# SolarPanelWithLongSide.net
KiCad netlist of a schematic drawn in Altium Designer
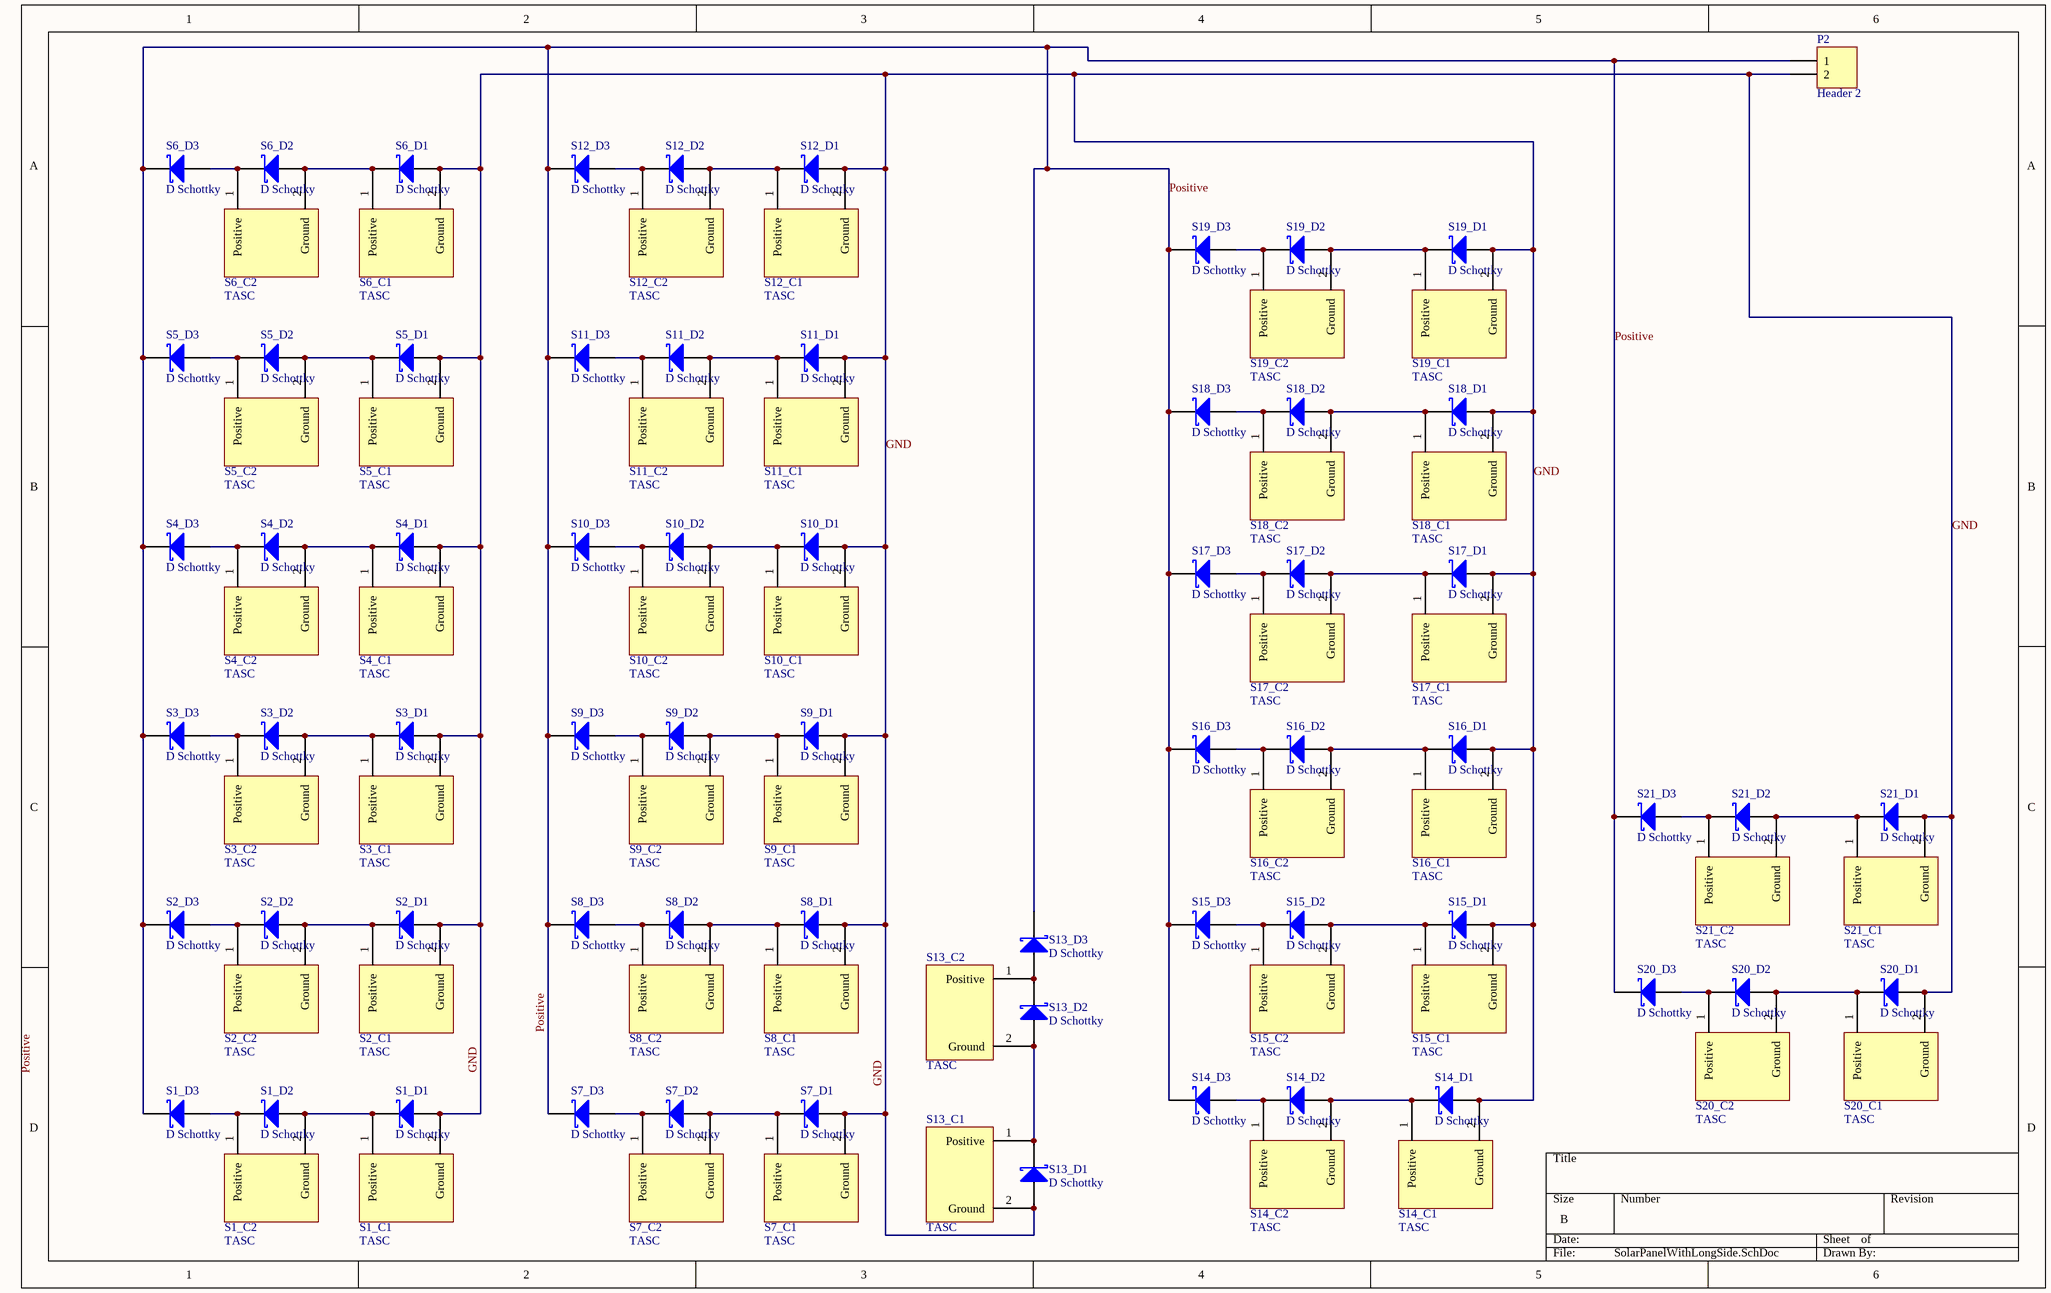
[diagram p0: SolarPanelWithLongSide.SchDoc]

(export (version "E")
  (design (tool "Eeschema 10.0.6"))
  (components
    (comp (ref "P2")
      (value "Header 2")
      (footprint "HDR1X2")
      (description "Header, 2-Pin")
      (fields (field (name "PUBLISHER") "Altium Limited"))
      (libsource (lib "Miscellaneous Connectors") (part "Header 2"))
    )
    (comp (ref "S1_C1")
      (value "TASC")
      (footprint "PCBComponent_1")
      (description "TASC Solar Cell")
      (libsource (lib "SolarPanel1") (part "TASC"))
    )
    (comp (ref "S1_C2")
      (value "TASC")
      (footprint "PCBComponent_1")
      (description "TASC Solar Cell")
      (libsource (lib "SolarPanel1") (part "TASC"))
    )
    (comp (ref "S1_D1")
      (value "D Schottky")
      (footprint "SMB")
      (description "Schottky Diode")
      (fields (field (name "PUBLISHER") "Altium Limited"))
      (libsource (lib "Miscellaneous Devices") (part "D Schottky"))
    )
    (comp (ref "S1_D2")
      (value "D Schottky")
      (footprint "SMB")
      (description "Schottky Diode")
      (fields (field (name "PUBLISHER") "Altium Limited"))
      (libsource (lib "Miscellaneous Devices") (part "D Schottky"))
    )
    (comp (ref "S1_D3")
      (value "D Schottky")
      (footprint "SMB")
      (description "Schottky Diode")
      (fields (field (name "PUBLISHER") "Altium Limited"))
      (libsource (lib "Miscellaneous Devices") (part "D Schottky"))
    )
    (comp (ref "S2_C1")
      (value "TASC")
      (footprint "PCBComponent_1")
      (description "TASC Solar Cell")
      (libsource (lib "SolarPanel1") (part "TASC"))
    )
    (comp (ref "S2_C2")
      (value "TASC")
      (footprint "PCBComponent_1")
      (description "TASC Solar Cell")
      (libsource (lib "SolarPanel1") (part "TASC"))
    )
    (comp (ref "S2_D1")
      (value "D Schottky")
      (footprint "SMB")
      (description "Schottky Diode")
      (fields (field (name "PUBLISHER") "Altium Limited"))
      (libsource (lib "Miscellaneous Devices") (part "D Schottky"))
    )
    (comp (ref "S2_D2")
      (value "D Schottky")
      (footprint "SMB")
      (description "Schottky Diode")
      (fields (field (name "PUBLISHER") "Altium Limited"))
      (libsource (lib "Miscellaneous Devices") (part "D Schottky"))
    )
    (comp (ref "S2_D3")
      (value "D Schottky")
      (footprint "SMB")
      (description "Schottky Diode")
      (fields (field (name "PUBLISHER") "Altium Limited"))
      (libsource (lib "Miscellaneous Devices") (part "D Schottky"))
    )
    (comp (ref "S3_C1")
      (value "TASC")
      (footprint "PCBComponent_1")
      (description "TASC Solar Cell")
      (libsource (lib "SolarPanel1") (part "TASC"))
    )
    (comp (ref "S3_C2")
      (value "TASC")
      (footprint "PCBComponent_1")
      (description "TASC Solar Cell")
      (libsource (lib "SolarPanel1") (part "TASC"))
    )
    (comp (ref "S3_D1")
      (value "D Schottky")
      (footprint "SMB")
      (description "Schottky Diode")
      (fields (field (name "PUBLISHER") "Altium Limited"))
      (libsource (lib "Miscellaneous Devices") (part "D Schottky"))
    )
    (comp (ref "S3_D2")
      (value "D Schottky")
      (footprint "SMB")
      (description "Schottky Diode")
      (fields (field (name "PUBLISHER") "Altium Limited"))
      (libsource (lib "Miscellaneous Devices") (part "D Schottky"))
    )
    (comp (ref "S3_D3")
      (value "D Schottky")
      (footprint "SMB")
      (description "Schottky Diode")
      (fields (field (name "PUBLISHER") "Altium Limited"))
      (libsource (lib "Miscellaneous Devices") (part "D Schottky"))
    )
    (comp (ref "S4_C1")
      (value "TASC")
      (footprint "PCBComponent_1")
      (description "TASC Solar Cell")
      (libsource (lib "SolarPanel1") (part "TASC"))
    )
    (comp (ref "S4_C2")
      (value "TASC")
      (footprint "PCBComponent_1")
      (description "TASC Solar Cell")
      (libsource (lib "SolarPanel1") (part "TASC"))
    )
    (comp (ref "S4_D1")
      (value "D Schottky")
      (footprint "SMB")
      (description "Schottky Diode")
      (fields (field (name "PUBLISHER") "Altium Limited"))
      (libsource (lib "Miscellaneous Devices") (part "D Schottky"))
    )
    (comp (ref "S4_D2")
      (value "D Schottky")
      (footprint "SMB")
      (description "Schottky Diode")
      (fields (field (name "PUBLISHER") "Altium Limited"))
      (libsource (lib "Miscellaneous Devices") (part "D Schottky"))
    )
    (comp (ref "S4_D3")
      (value "D Schottky")
      (footprint "SMB")
      (description "Schottky Diode")
      (fields (field (name "PUBLISHER") "Altium Limited"))
      (libsource (lib "Miscellaneous Devices") (part "D Schottky"))
    )
    (comp (ref "S5_C1")
      (value "TASC")
      (footprint "PCBComponent_1")
      (description "TASC Solar Cell")
      (libsource (lib "SolarPanel1") (part "TASC"))
    )
    (comp (ref "S5_C2")
      (value "TASC")
      (footprint "PCBComponent_1")
      (description "TASC Solar Cell")
      (libsource (lib "SolarPanel1") (part "TASC"))
    )
    (comp (ref "S5_D1")
      (value "D Schottky")
      (footprint "SMB")
      (description "Schottky Diode")
      (fields (field (name "PUBLISHER") "Altium Limited"))
      (libsource (lib "Miscellaneous Devices") (part "D Schottky"))
    )
    (comp (ref "S5_D2")
      (value "D Schottky")
      (footprint "SMB")
      (description "Schottky Diode")
      (fields (field (name "PUBLISHER") "Altium Limited"))
      (libsource (lib "Miscellaneous Devices") (part "D Schottky"))
    )
    (comp (ref "S5_D3")
      (value "D Schottky")
      (footprint "SMB")
      (description "Schottky Diode")
      (fields (field (name "PUBLISHER") "Altium Limited"))
      (libsource (lib "Miscellaneous Devices") (part "D Schottky"))
    )
    (comp (ref "S6_C1")
      (value "TASC")
      (footprint "PCBComponent_1")
      (description "TASC Solar Cell")
      (libsource (lib "SolarPanel1") (part "TASC"))
    )
    (comp (ref "S6_C2")
      (value "TASC")
      (footprint "PCBComponent_1")
      (description "TASC Solar Cell")
      (libsource (lib "SolarPanel1") (part "TASC"))
    )
    (comp (ref "S6_D1")
      (value "D Schottky")
      (footprint "SMB")
      (description "Schottky Diode")
      (fields (field (name "PUBLISHER") "Altium Limited"))
      (libsource (lib "Miscellaneous Devices") (part "D Schottky"))
    )
    (comp (ref "S6_D2")
      (value "D Schottky")
      (footprint "SMB")
      (description "Schottky Diode")
      (fields (field (name "PUBLISHER") "Altium Limited"))
      (libsource (lib "Miscellaneous Devices") (part "D Schottky"))
    )
    (comp (ref "S6_D3")
      (value "D Schottky")
      (footprint "SMB")
      (description "Schottky Diode")
      (fields (field (name "PUBLISHER") "Altium Limited"))
      (libsource (lib "Miscellaneous Devices") (part "D Schottky"))
    )
    (comp (ref "S7_C1")
      (value "TASC")
      (footprint "PCBComponent_1")
      (description "TASC Solar Cell")
      (libsource (lib "SolarPanel1") (part "TASC"))
    )
    (comp (ref "S7_C2")
      (value "TASC")
      (footprint "PCBComponent_1")
      (description "TASC Solar Cell")
      (libsource (lib "SolarPanel1") (part "TASC"))
    )
    (comp (ref "S7_D1")
      (value "D Schottky")
      (footprint "SMB")
      (description "Schottky Diode")
      (fields (field (name "PUBLISHER") "Altium Limited"))
      (libsource (lib "Miscellaneous Devices") (part "D Schottky"))
    )
    (comp (ref "S7_D2")
      (value "D Schottky")
      (footprint "SMB")
      (description "Schottky Diode")
      (fields (field (name "PUBLISHER") "Altium Limited"))
      (libsource (lib "Miscellaneous Devices") (part "D Schottky"))
    )
    (comp (ref "S7_D3")
      (value "D Schottky")
      (footprint "SMB")
      (description "Schottky Diode")
      (fields (field (name "PUBLISHER") "Altium Limited"))
      (libsource (lib "Miscellaneous Devices") (part "D Schottky"))
    )
    (comp (ref "S8_C1")
      (value "TASC")
      (footprint "PCBComponent_1")
      (description "TASC Solar Cell")
      (libsource (lib "SolarPanel1") (part "TASC"))
    )
    (comp (ref "S8_C2")
      (value "TASC")
      (footprint "PCBComponent_1")
      (description "TASC Solar Cell")
      (libsource (lib "SolarPanel1") (part "TASC"))
    )
    (comp (ref "S8_D1")
      (value "D Schottky")
      (footprint "SMB")
      (description "Schottky Diode")
      (fields (field (name "PUBLISHER") "Altium Limited"))
      (libsource (lib "Miscellaneous Devices") (part "D Schottky"))
    )
    (comp (ref "S8_D2")
      (value "D Schottky")
      (footprint "SMB")
      (description "Schottky Diode")
      (fields (field (name "PUBLISHER") "Altium Limited"))
      (libsource (lib "Miscellaneous Devices") (part "D Schottky"))
    )
    (comp (ref "S8_D3")
      (value "D Schottky")
      (footprint "SMB")
      (description "Schottky Diode")
      (fields (field (name "PUBLISHER") "Altium Limited"))
      (libsource (lib "Miscellaneous Devices") (part "D Schottky"))
    )
    (comp (ref "S9_C1")
      (value "TASC")
      (footprint "PCBComponent_1")
      (description "TASC Solar Cell")
      (libsource (lib "SolarPanel1") (part "TASC"))
    )
    (comp (ref "S9_C2")
      (value "TASC")
      (footprint "PCBComponent_1")
      (description "TASC Solar Cell")
      (libsource (lib "SolarPanel1") (part "TASC"))
    )
    (comp (ref "S9_D1")
      (value "D Schottky")
      (footprint "SMB")
      (description "Schottky Diode")
      (fields (field (name "PUBLISHER") "Altium Limited"))
      (libsource (lib "Miscellaneous Devices") (part "D Schottky"))
    )
    (comp (ref "S9_D2")
      (value "D Schottky")
      (footprint "SMB")
      (description "Schottky Diode")
      (fields (field (name "PUBLISHER") "Altium Limited"))
      (libsource (lib "Miscellaneous Devices") (part "D Schottky"))
    )
    (comp (ref "S9_D3")
      (value "D Schottky")
      (footprint "SMB")
      (description "Schottky Diode")
      (fields (field (name "PUBLISHER") "Altium Limited"))
      (libsource (lib "Miscellaneous Devices") (part "D Schottky"))
    )
    (comp (ref "S10_C1")
      (value "TASC")
      (footprint "PCBComponent_1")
      (description "TASC Solar Cell")
      (libsource (lib "SolarPanel1") (part "TASC"))
    )
    (comp (ref "S10_C2")
      (value "TASC")
      (footprint "PCBComponent_1")
      (description "TASC Solar Cell")
      (libsource (lib "SolarPanel1") (part "TASC"))
    )
    (comp (ref "S10_D1")
      (value "D Schottky")
      (footprint "SMB")
      (description "Schottky Diode")
      (fields (field (name "PUBLISHER") "Altium Limited"))
      (libsource (lib "Miscellaneous Devices") (part "D Schottky"))
    )
    (comp (ref "S10_D2")
      (value "D Schottky")
      (footprint "SMB")
      (description "Schottky Diode")
      (fields (field (name "PUBLISHER") "Altium Limited"))
      (libsource (lib "Miscellaneous Devices") (part "D Schottky"))
    )
    (comp (ref "S10_D3")
      (value "D Schottky")
      (footprint "SMB")
      (description "Schottky Diode")
      (fields (field (name "PUBLISHER") "Altium Limited"))
      (libsource (lib "Miscellaneous Devices") (part "D Schottky"))
    )
    (comp (ref "S11_C1")
      (value "TASC")
      (footprint "PCBComponent_1")
      (description "TASC Solar Cell")
      (libsource (lib "SolarPanel1") (part "TASC"))
    )
    (comp (ref "S11_C2")
      (value "TASC")
      (footprint "PCBComponent_1")
      (description "TASC Solar Cell")
      (libsource (lib "SolarPanel1") (part "TASC"))
    )
    (comp (ref "S11_D1")
      (value "D Schottky")
      (footprint "SMB")
      (description "Schottky Diode")
      (fields (field (name "PUBLISHER") "Altium Limited"))
      (libsource (lib "Miscellaneous Devices") (part "D Schottky"))
    )
    (comp (ref "S11_D2")
      (value "D Schottky")
      (footprint "SMB")
      (description "Schottky Diode")
      (fields (field (name "PUBLISHER") "Altium Limited"))
      (libsource (lib "Miscellaneous Devices") (part "D Schottky"))
    )
    (comp (ref "S11_D3")
      (value "D Schottky")
      (footprint "SMB")
      (description "Schottky Diode")
      (fields (field (name "PUBLISHER") "Altium Limited"))
      (libsource (lib "Miscellaneous Devices") (part "D Schottky"))
    )
    (comp (ref "S12_C1")
      (value "TASC")
      (footprint "PCBComponent_1")
      (description "TASC Solar Cell")
      (libsource (lib "SolarPanel1") (part "TASC"))
    )
    (comp (ref "S12_C2")
      (value "TASC")
      (footprint "PCBComponent_1")
      (description "TASC Solar Cell")
      (libsource (lib "SolarPanel1") (part "TASC"))
    )
    (comp (ref "S12_D1")
      (value "D Schottky")
      (footprint "SMB")
      (description "Schottky Diode")
      (fields (field (name "PUBLISHER") "Altium Limited"))
      (libsource (lib "Miscellaneous Devices") (part "D Schottky"))
    )
    (comp (ref "S12_D2")
      (value "D Schottky")
      (footprint "SMB")
      (description "Schottky Diode")
      (fields (field (name "PUBLISHER") "Altium Limited"))
      (libsource (lib "Miscellaneous Devices") (part "D Schottky"))
    )
    (comp (ref "S12_D3")
      (value "D Schottky")
      (footprint "SMB")
      (description "Schottky Diode")
      (fields (field (name "PUBLISHER") "Altium Limited"))
      (libsource (lib "Miscellaneous Devices") (part "D Schottky"))
    )
    (comp (ref "S13_C1")
      (value "TASC")
      (footprint "PCBComponent_1")
      (description "TASC Solar Cell")
      (libsource (lib "") (part "TASC_1"))
    )
    (comp (ref "S13_C2")
      (value "TASC")
      (footprint "PCBComponent_1")
      (description "TASC Solar Cell")
      (libsource (lib "") (part "TASC_1"))
    )
    (comp (ref "S13_D1")
      (value "D Schottky")
      (footprint "SMB")
      (description "Schottky Diode")
      (fields (field (name "PUBLISHER") "Altium Limited"))
      (libsource (lib "Miscellaneous Devices") (part "D Schottky"))
    )
    (comp (ref "S13_D2")
      (value "D Schottky")
      (footprint "SMB")
      (description "Schottky Diode")
      (fields (field (name "PUBLISHER") "Altium Limited"))
      (libsource (lib "Miscellaneous Devices") (part "D Schottky"))
    )
    (comp (ref "S13_D3")
      (value "D Schottky")
      (footprint "SMB")
      (description "Schottky Diode")
      (fields (field (name "PUBLISHER") "Altium Limited"))
      (libsource (lib "Miscellaneous Devices") (part "D Schottky"))
    )
    (comp (ref "S14_C1")
      (value "TASC")
      (footprint "PCBComponent_1")
      (description "TASC Solar Cell")
      (libsource (lib "SolarPanel1") (part "TASC"))
    )
    (comp (ref "S14_C2")
      (value "TASC")
      (footprint "PCBComponent_1")
      (description "TASC Solar Cell")
      (libsource (lib "SolarPanel1") (part "TASC"))
    )
    (comp (ref "S14_D1")
      (value "D Schottky")
      (footprint "SMB")
      (description "Schottky Diode")
      (fields (field (name "PUBLISHER") "Altium Limited"))
      (libsource (lib "Miscellaneous Devices") (part "D Schottky"))
    )
    (comp (ref "S14_D2")
      (value "D Schottky")
      (footprint "SMB")
      (description "Schottky Diode")
      (fields (field (name "PUBLISHER") "Altium Limited"))
      (libsource (lib "Miscellaneous Devices") (part "D Schottky"))
    )
    (comp (ref "S14_D3")
      (value "D Schottky")
      (footprint "SMB")
      (description "Schottky Diode")
      (fields (field (name "PUBLISHER") "Altium Limited"))
      (libsource (lib "Miscellaneous Devices") (part "D Schottky"))
    )
    (comp (ref "S15_C1")
      (value "TASC")
      (footprint "PCBComponent_1")
      (description "TASC Solar Cell")
      (libsource (lib "SolarPanel1") (part "TASC"))
    )
    (comp (ref "S15_C2")
      (value "TASC")
      (footprint "PCBComponent_1")
      (description "TASC Solar Cell")
      (libsource (lib "SolarPanel1") (part "TASC"))
    )
    (comp (ref "S15_D1")
      (value "D Schottky")
      (footprint "SMB")
      (description "Schottky Diode")
      (fields (field (name "PUBLISHER") "Altium Limited"))
      (libsource (lib "Miscellaneous Devices") (part "D Schottky"))
    )
    (comp (ref "S15_D2")
      (value "D Schottky")
      (footprint "SMB")
      (description "Schottky Diode")
      (fields (field (name "PUBLISHER") "Altium Limited"))
      (libsource (lib "Miscellaneous Devices") (part "D Schottky"))
    )
    (comp (ref "S15_D3")
      (value "D Schottky")
      (footprint "SMB")
      (description "Schottky Diode")
      (fields (field (name "PUBLISHER") "Altium Limited"))
      (libsource (lib "Miscellaneous Devices") (part "D Schottky"))
    )
    (comp (ref "S16_C1")
      (value "TASC")
      (footprint "PCBComponent_1")
      (description "TASC Solar Cell")
      (libsource (lib "SolarPanel1") (part "TASC"))
    )
    (comp (ref "S16_C2")
      (value "TASC")
      (footprint "PCBComponent_1")
      (description "TASC Solar Cell")
      (libsource (lib "SolarPanel1") (part "TASC"))
    )
    (comp (ref "S16_D1")
      (value "D Schottky")
      (footprint "SMB")
      (description "Schottky Diode")
      (fields (field (name "PUBLISHER") "Altium Limited"))
      (libsource (lib "Miscellaneous Devices") (part "D Schottky"))
    )
    (comp (ref "S16_D2")
      (value "D Schottky")
      (footprint "SMB")
      (description "Schottky Diode")
      (fields (field (name "PUBLISHER") "Altium Limited"))
      (libsource (lib "Miscellaneous Devices") (part "D Schottky"))
    )
    (comp (ref "S16_D3")
      (value "D Schottky")
      (footprint "SMB")
      (description "Schottky Diode")
      (fields (field (name "PUBLISHER") "Altium Limited"))
      (libsource (lib "Miscellaneous Devices") (part "D Schottky"))
    )
    (comp (ref "S17_C1")
      (value "TASC")
      (footprint "PCBComponent_1")
      (description "TASC Solar Cell")
      (libsource (lib "SolarPanel1") (part "TASC"))
    )
    (comp (ref "S17_C2")
      (value "TASC")
      (footprint "PCBComponent_1")
      (description "TASC Solar Cell")
      (libsource (lib "SolarPanel1") (part "TASC"))
    )
    (comp (ref "S17_D1")
      (value "D Schottky")
      (footprint "SMB")
      (description "Schottky Diode")
      (fields (field (name "PUBLISHER") "Altium Limited"))
      (libsource (lib "Miscellaneous Devices") (part "D Schottky"))
    )
    (comp (ref "S17_D2")
      (value "D Schottky")
      (footprint "SMB")
      (description "Schottky Diode")
      (fields (field (name "PUBLISHER") "Altium Limited"))
      (libsource (lib "Miscellaneous Devices") (part "D Schottky"))
    )
    (comp (ref "S17_D3")
      (value "D Schottky")
      (footprint "SMB")
      (description "Schottky Diode")
      (fields (field (name "PUBLISHER") "Altium Limited"))
      (libsource (lib "Miscellaneous Devices") (part "D Schottky"))
    )
    (comp (ref "S18_C1")
      (value "TASC")
      (footprint "PCBComponent_1")
      (description "TASC Solar Cell")
      (libsource (lib "SolarPanel1") (part "TASC"))
    )
    (comp (ref "S18_C2")
      (value "TASC")
      (footprint "PCBComponent_1")
      (description "TASC Solar Cell")
      (libsource (lib "SolarPanel1") (part "TASC"))
    )
    (comp (ref "S18_D1")
      (value "D Schottky")
      (footprint "SMB")
      (description "Schottky Diode")
      (fields (field (name "PUBLISHER") "Altium Limited"))
      (libsource (lib "Miscellaneous Devices") (part "D Schottky"))
    )
    (comp (ref "S18_D2")
      (value "D Schottky")
      (footprint "SMB")
      (description "Schottky Diode")
      (fields (field (name "PUBLISHER") "Altium Limited"))
      (libsource (lib "Miscellaneous Devices") (part "D Schottky"))
    )
    (comp (ref "S18_D3")
      (value "D Schottky")
      (footprint "SMB")
      (description "Schottky Diode")
      (fields (field (name "PUBLISHER") "Altium Limited"))
      (libsource (lib "Miscellaneous Devices") (part "D Schottky"))
    )
    (comp (ref "S19_C1")
      (value "TASC")
      (footprint "PCBComponent_1")
      (description "TASC Solar Cell")
      (libsource (lib "SolarPanel1") (part "TASC"))
    )
    (comp (ref "S19_C2")
      (value "TASC")
      (footprint "PCBComponent_1")
      (description "TASC Solar Cell")
      (libsource (lib "SolarPanel1") (part "TASC"))
    )
    (comp (ref "S19_D1")
      (value "D Schottky")
      (footprint "SMB")
      (description "Schottky Diode")
      (fields (field (name "PUBLISHER") "Altium Limited"))
      (libsource (lib "Miscellaneous Devices") (part "D Schottky"))
    )
    (comp (ref "S19_D2")
      (value "D Schottky")
      (footprint "SMB")
      (description "Schottky Diode")
      (fields (field (name "PUBLISHER") "Altium Limited"))
      (libsource (lib "Miscellaneous Devices") (part "D Schottky"))
    )
    (comp (ref "S19_D3")
      (value "D Schottky")
      (footprint "SMB")
      (description "Schottky Diode")
      (fields (field (name "PUBLISHER") "Altium Limited"))
      (libsource (lib "Miscellaneous Devices") (part "D Schottky"))
    )
    (comp (ref "S20_C1")
      (value "TASC")
      (footprint "PCBComponent_1")
      (description "TASC Solar Cell")
      (libsource (lib "SolarPanel1") (part "TASC"))
    )
    (comp (ref "S20_C2")
      (value "TASC")
      (footprint "PCBComponent_1")
      (description "TASC Solar Cell")
      (libsource (lib "SolarPanel1") (part "TASC"))
    )
    (comp (ref "S20_D1")
      (value "D Schottky")
      (footprint "SMB")
      (description "Schottky Diode")
      (fields (field (name "PUBLISHER") "Altium Limited"))
      (libsource (lib "Miscellaneous Devices") (part "D Schottky"))
    )
    (comp (ref "S20_D2")
      (value "D Schottky")
      (footprint "SMB")
      (description "Schottky Diode")
      (fields (field (name "PUBLISHER") "Altium Limited"))
      (libsource (lib "Miscellaneous Devices") (part "D Schottky"))
    )
    (comp (ref "S20_D3")
      (value "D Schottky")
      (footprint "SMB")
      (description "Schottky Diode")
      (fields (field (name "PUBLISHER") "Altium Limited"))
      (libsource (lib "Miscellaneous Devices") (part "D Schottky"))
    )
    (comp (ref "S21_C1")
      (value "TASC")
      (footprint "PCBComponent_1")
      (description "TASC Solar Cell")
      (libsource (lib "SolarPanel1") (part "TASC"))
    )
    (comp (ref "S21_C2")
      (value "TASC")
      (footprint "PCBComponent_1")
      (description "TASC Solar Cell")
      (libsource (lib "SolarPanel1") (part "TASC"))
    )
    (comp (ref "S21_D1")
      (value "D Schottky")
      (footprint "SMB")
      (description "Schottky Diode")
      (fields (field (name "PUBLISHER") "Altium Limited"))
      (libsource (lib "Miscellaneous Devices") (part "D Schottky"))
    )
    (comp (ref "S21_D2")
      (value "D Schottky")
      (footprint "SMB")
      (description "Schottky Diode")
      (fields (field (name "PUBLISHER") "Altium Limited"))
      (libsource (lib "Miscellaneous Devices") (part "D Schottky"))
    )
    (comp (ref "S21_D3")
      (value "D Schottky")
      (footprint "SMB")
      (description "Schottky Diode")
      (fields (field (name "PUBLISHER") "Altium Limited"))
      (libsource (lib "Miscellaneous Devices") (part "D Schottky"))
    )
  )
  (nets
    (net (code "1") (name "/GND") (class "Default")
      (node (ref "P2") (pin "2") (pinfunction "2_2") (pintype "passive"))
      (node (ref "S10_C1") (pin "2") (pinfunction "Ground_2") (pintype "power_in"))
      (node (ref "S10_D1") (pin "1") (pinfunction "A_1") (pintype "passive"))
      (node (ref "S11_C1") (pin "2") (pinfunction "Ground_2") (pintype "power_in"))
      (node (ref "S11_D1") (pin "1") (pinfunction "A_1") (pintype "passive"))
      (node (ref "S12_C1") (pin "2") (pinfunction "Ground_2") (pintype "power_in"))
      (node (ref "S12_D1") (pin "1") (pinfunction "A_1") (pintype "passive"))
      (node (ref "S13_C1") (pin "2") (pinfunction "Ground_2") (pintype "power_in"))
      (node (ref "S13_D1") (pin "1") (pinfunction "A_1") (pintype "passive"))
      (node (ref "S14_C1") (pin "2") (pinfunction "Ground_2") (pintype "power_in"))
      (node (ref "S14_D1") (pin "1") (pinfunction "A_1") (pintype "passive"))
      (node (ref "S15_C1") (pin "2") (pinfunction "Ground_2") (pintype "power_in"))
      (node (ref "S15_D1") (pin "1") (pinfunction "A_1") (pintype "passive"))
      (node (ref "S16_C1") (pin "2") (pinfunction "Ground_2") (pintype "power_in"))
      (node (ref "S16_D1") (pin "1") (pinfunction "A_1") (pintype "passive"))
      (node (ref "S17_C1") (pin "2") (pinfunction "Ground_2") (pintype "power_in"))
      (node (ref "S17_D1") (pin "1") (pinfunction "A_1") (pintype "passive"))
      (node (ref "S18_C1") (pin "2") (pinfunction "Ground_2") (pintype "power_in"))
      (node (ref "S18_D1") (pin "1") (pinfunction "A_1") (pintype "passive"))
      (node (ref "S19_C1") (pin "2") (pinfunction "Ground_2") (pintype "power_in"))
      (node (ref "S19_D1") (pin "1") (pinfunction "A_1") (pintype "passive"))
      (node (ref "S1_C1") (pin "2") (pinfunction "Ground_2") (pintype "power_in"))
      (node (ref "S1_D1") (pin "1") (pinfunction "A_1") (pintype "passive"))
      (node (ref "S20_C1") (pin "2") (pinfunction "Ground_2") (pintype "power_in"))
      (node (ref "S20_D1") (pin "1") (pinfunction "A_1") (pintype "passive"))
      (node (ref "S21_C1") (pin "2") (pinfunction "Ground_2") (pintype "power_in"))
      (node (ref "S21_D1") (pin "1") (pinfunction "A_1") (pintype "passive"))
      (node (ref "S2_C1") (pin "2") (pinfunction "Ground_2") (pintype "power_in"))
      (node (ref "S2_D1") (pin "1") (pinfunction "A_1") (pintype "passive"))
      (node (ref "S3_C1") (pin "2") (pinfunction "Ground_2") (pintype "power_in"))
      (node (ref "S3_D1") (pin "1") (pinfunction "A_1") (pintype "passive"))
      (node (ref "S4_C1") (pin "2") (pinfunction "Ground_2") (pintype "power_in"))
      (node (ref "S4_D1") (pin "1") (pinfunction "A_1") (pintype "passive"))
      (node (ref "S5_C1") (pin "2") (pinfunction "Ground_2") (pintype "power_in"))
      (node (ref "S5_D1") (pin "1") (pinfunction "A_1") (pintype "passive"))
      (node (ref "S6_C1") (pin "2") (pinfunction "Ground_2") (pintype "power_in"))
      (node (ref "S6_D1") (pin "1") (pinfunction "A_1") (pintype "passive"))
      (node (ref "S7_C1") (pin "2") (pinfunction "Ground_2") (pintype "power_in"))
      (node (ref "S7_D1") (pin "1") (pinfunction "A_1") (pintype "passive"))
      (node (ref "S8_C1") (pin "2") (pinfunction "Ground_2") (pintype "power_in"))
      (node (ref "S8_D1") (pin "1") (pinfunction "A_1") (pintype "passive"))
      (node (ref "S9_C1") (pin "2") (pinfunction "Ground_2") (pintype "power_in"))
      (node (ref "S9_D1") (pin "1") (pinfunction "A_1") (pintype "passive"))
    )
    (net (code "2") (name "/Positive") (class "Default")
      (node (ref "P2") (pin "1") (pinfunction "1_1") (pintype "passive"))
      (node (ref "S10_D3") (pin "2") (pinfunction "K_2") (pintype "passive"))
      (node (ref "S11_D3") (pin "2") (pinfunction "K_2") (pintype "passive"))
      (node (ref "S12_D3") (pin "2") (pinfunction "K_2") (pintype "passive"))
      (node (ref "S13_D3") (pin "2") (pinfunction "K_2") (pintype "passive"))
      (node (ref "S14_D3") (pin "2") (pinfunction "K_2") (pintype "passive"))
      (node (ref "S15_D3") (pin "2") (pinfunction "K_2") (pintype "passive"))
      (node (ref "S16_D3") (pin "2") (pinfunction "K_2") (pintype "passive"))
      (node (ref "S17_D3") (pin "2") (pinfunction "K_2") (pintype "passive"))
      (node (ref "S18_D3") (pin "2") (pinfunction "K_2") (pintype "passive"))
      (node (ref "S19_D3") (pin "2") (pinfunction "K_2") (pintype "passive"))
      (node (ref "S1_D3") (pin "2") (pinfunction "K_2") (pintype "passive"))
      (node (ref "S20_D3") (pin "2") (pinfunction "K_2") (pintype "passive"))
      (node (ref "S21_D3") (pin "2") (pinfunction "K_2") (pintype "passive"))
      (node (ref "S2_D3") (pin "2") (pinfunction "K_2") (pintype "passive"))
      (node (ref "S3_D3") (pin "2") (pinfunction "K_2") (pintype "passive"))
      (node (ref "S4_D3") (pin "2") (pinfunction "K_2") (pintype "passive"))
      (node (ref "S5_D3") (pin "2") (pinfunction "K_2") (pintype "passive"))
      (node (ref "S6_D3") (pin "2") (pinfunction "K_2") (pintype "passive"))
      (node (ref "S7_D3") (pin "2") (pinfunction "K_2") (pintype "passive"))
      (node (ref "S8_D3") (pin "2") (pinfunction "K_2") (pintype "passive"))
      (node (ref "S9_D3") (pin "2") (pinfunction "K_2") (pintype "passive"))
    )
    (net (code "3") (name "Net-(S1_C1-Positive)") (class "Default")
      (node (ref "S1_C1") (pin "1") (pinfunction "Positive_1") (pintype "power_in"))
      (node (ref "S1_C2") (pin "2") (pinfunction "Ground_2") (pintype "power_in"))
      (node (ref "S1_D1") (pin "2") (pinfunction "K_2") (pintype "passive"))
      (node (ref "S1_D2") (pin "1") (pinfunction "A_1") (pintype "passive"))
    )
    (net (code "4") (name "Net-(S1_C2-Positive)") (class "Default")
      (node (ref "S1_C2") (pin "1") (pinfunction "Positive_1") (pintype "power_in"))
      (node (ref "S1_D2") (pin "2") (pinfunction "K_2") (pintype "passive"))
      (node (ref "S1_D3") (pin "1") (pinfunction "A_1") (pintype "passive"))
    )
    (net (code "5") (name "Net-(S2_C1-Positive)") (class "Default")
      (node (ref "S2_C1") (pin "1") (pinfunction "Positive_1") (pintype "power_in"))
      (node (ref "S2_C2") (pin "2") (pinfunction "Ground_2") (pintype "power_in"))
      (node (ref "S2_D1") (pin "2") (pinfunction "K_2") (pintype "passive"))
      (node (ref "S2_D2") (pin "1") (pinfunction "A_1") (pintype "passive"))
    )
    (net (code "6") (name "Net-(S2_C2-Positive)") (class "Default")
      (node (ref "S2_C2") (pin "1") (pinfunction "Positive_1") (pintype "power_in"))
      (node (ref "S2_D2") (pin "2") (pinfunction "K_2") (pintype "passive"))
      (node (ref "S2_D3") (pin "1") (pinfunction "A_1") (pintype "passive"))
    )
    (net (code "7") (name "Net-(S3_C1-Positive)") (class "Default")
      (node (ref "S3_C1") (pin "1") (pinfunction "Positive_1") (pintype "power_in"))
      (node (ref "S3_C2") (pin "2") (pinfunction "Ground_2") (pintype "power_in"))
      (node (ref "S3_D1") (pin "2") (pinfunction "K_2") (pintype "passive"))
      (node (ref "S3_D2") (pin "1") (pinfunction "A_1") (pintype "passive"))
    )
    (net (code "8") (name "Net-(S3_C2-Positive)") (class "Default")
      (node (ref "S3_C2") (pin "1") (pinfunction "Positive_1") (pintype "power_in"))
      (node (ref "S3_D2") (pin "2") (pinfunction "K_2") (pintype "passive"))
      (node (ref "S3_D3") (pin "1") (pinfunction "A_1") (pintype "passive"))
    )
    (net (code "9") (name "Net-(S4_C1-Positive)") (class "Default")
      (node (ref "S4_C1") (pin "1") (pinfunction "Positive_1") (pintype "power_in"))
      (node (ref "S4_C2") (pin "2") (pinfunction "Ground_2") (pintype "power_in"))
      (node (ref "S4_D1") (pin "2") (pinfunction "K_2") (pintype "passive"))
      (node (ref "S4_D2") (pin "1") (pinfunction "A_1") (pintype "passive"))
    )
    (net (code "10") (name "Net-(S4_C2-Positive)") (class "Default")
      (node (ref "S4_C2") (pin "1") (pinfunction "Positive_1") (pintype "power_in"))
      (node (ref "S4_D2") (pin "2") (pinfunction "K_2") (pintype "passive"))
      (node (ref "S4_D3") (pin "1") (pinfunction "A_1") (pintype "passive"))
    )
    (net (code "11") (name "Net-(S5_C1-Positive)") (class "Default")
      (node (ref "S5_C1") (pin "1") (pinfunction "Positive_1") (pintype "power_in"))
      (node (ref "S5_C2") (pin "2") (pinfunction "Ground_2") (pintype "power_in"))
      (node (ref "S5_D1") (pin "2") (pinfunction "K_2") (pintype "passive"))
      (node (ref "S5_D2") (pin "1") (pinfunction "A_1") (pintype "passive"))
    )
    (net (code "12") (name "Net-(S5_C2-Positive)") (class "Default")
      (node (ref "S5_C2") (pin "1") (pinfunction "Positive_1") (pintype "power_in"))
      (node (ref "S5_D2") (pin "2") (pinfunction "K_2") (pintype "passive"))
      (node (ref "S5_D3") (pin "1") (pinfunction "A_1") (pintype "passive"))
    )
    (net (code "13") (name "Net-(S6_C1-Positive)") (class "Default")
      (node (ref "S6_C1") (pin "1") (pinfunction "Positive_1") (pintype "power_in"))
      (node (ref "S6_C2") (pin "2") (pinfunction "Ground_2") (pintype "power_in"))
      (node (ref "S6_D1") (pin "2") (pinfunction "K_2") (pintype "passive"))
      (node (ref "S6_D2") (pin "1") (pinfunction "A_1") (pintype "passive"))
    )
    (net (code "14") (name "Net-(S6_C2-Positive)") (class "Default")
      (node (ref "S6_C2") (pin "1") (pinfunction "Positive_1") (pintype "power_in"))
      (node (ref "S6_D2") (pin "2") (pinfunction "K_2") (pintype "passive"))
      (node (ref "S6_D3") (pin "1") (pinfunction "A_1") (pintype "passive"))
    )
    (net (code "15") (name "Net-(S7_C1-Positive)") (class "Default")
      (node (ref "S7_C1") (pin "1") (pinfunction "Positive_1") (pintype "power_in"))
      (node (ref "S7_C2") (pin "2") (pinfunction "Ground_2") (pintype "power_in"))
      (node (ref "S7_D1") (pin "2") (pinfunction "K_2") (pintype "passive"))
      (node (ref "S7_D2") (pin "1") (pinfunction "A_1") (pintype "passive"))
    )
    (net (code "16") (name "Net-(S7_C2-Positive)") (class "Default")
      (node (ref "S7_C2") (pin "1") (pinfunction "Positive_1") (pintype "power_in"))
      (node (ref "S7_D2") (pin "2") (pinfunction "K_2") (pintype "passive"))
      (node (ref "S7_D3") (pin "1") (pinfunction "A_1") (pintype "passive"))
    )
    (net (code "17") (name "Net-(S8_C1-Positive)") (class "Default")
      (node (ref "S8_C1") (pin "1") (pinfunction "Positive_1") (pintype "power_in"))
      (node (ref "S8_C2") (pin "2") (pinfunction "Ground_2") (pintype "power_in"))
      (node (ref "S8_D1") (pin "2") (pinfunction "K_2") (pintype "passive"))
      (node (ref "S8_D2") (pin "1") (pinfunction "A_1") (pintype "passive"))
    )
    (net (code "18") (name "Net-(S8_C2-Positive)") (class "Default")
      (node (ref "S8_C2") (pin "1") (pinfunction "Positive_1") (pintype "power_in"))
      (node (ref "S8_D2") (pin "2") (pinfunction "K_2") (pintype "passive"))
      (node (ref "S8_D3") (pin "1") (pinfunction "A_1") (pintype "passive"))
    )
    (net (code "19") (name "Net-(S9_C1-Positive)") (class "Default")
      (node (ref "S9_C1") (pin "1") (pinfunction "Positive_1") (pintype "power_in"))
      (node (ref "S9_C2") (pin "2") (pinfunction "Ground_2") (pintype "power_in"))
      (node (ref "S9_D1") (pin "2") (pinfunction "K_2") (pintype "passive"))
      (node (ref "S9_D2") (pin "1") (pinfunction "A_1") (pintype "passive"))
    )
    (net (code "20") (name "Net-(S9_C2-Positive)") (class "Default")
      (node (ref "S9_C2") (pin "1") (pinfunction "Positive_1") (pintype "power_in"))
      (node (ref "S9_D2") (pin "2") (pinfunction "K_2") (pintype "passive"))
      (node (ref "S9_D3") (pin "1") (pinfunction "A_1") (pintype "passive"))
    )
    (net (code "21") (name "Net-(S10_C1-Positive)") (class "Default")
      (node (ref "S10_C1") (pin "1") (pinfunction "Positive_1") (pintype "power_in"))
      (node (ref "S10_C2") (pin "2") (pinfunction "Ground_2") (pintype "power_in"))
      (node (ref "S10_D1") (pin "2") (pinfunction "K_2") (pintype "passive"))
      (node (ref "S10_D2") (pin "1") (pinfunction "A_1") (pintype "passive"))
    )
    (net (code "22") (name "Net-(S10_C2-Positive)") (class "Default")
      (node (ref "S10_C2") (pin "1") (pinfunction "Positive_1") (pintype "power_in"))
      (node (ref "S10_D2") (pin "2") (pinfunction "K_2") (pintype "passive"))
      (node (ref "S10_D3") (pin "1") (pinfunction "A_1") (pintype "passive"))
    )
    (net (code "23") (name "Net-(S11_C1-Positive)") (class "Default")
      (node (ref "S11_C1") (pin "1") (pinfunction "Positive_1") (pintype "power_in"))
      (node (ref "S11_C2") (pin "2") (pinfunction "Ground_2") (pintype "power_in"))
      (node (ref "S11_D1") (pin "2") (pinfunction "K_2") (pintype "passive"))
      (node (ref "S11_D2") (pin "1") (pinfunction "A_1") (pintype "passive"))
    )
    (net (code "24") (name "Net-(S11_C2-Positive)") (class "Default")
      (node (ref "S11_C2") (pin "1") (pinfunction "Positive_1") (pintype "power_in"))
      (node (ref "S11_D2") (pin "2") (pinfunction "K_2") (pintype "passive"))
      (node (ref "S11_D3") (pin "1") (pinfunction "A_1") (pintype "passive"))
    )
    (net (code "25") (name "Net-(S12_C1-Positive)") (class "Default")
      (node (ref "S12_C1") (pin "1") (pinfunction "Positive_1") (pintype "power_in"))
      (node (ref "S12_C2") (pin "2") (pinfunction "Ground_2") (pintype "power_in"))
      (node (ref "S12_D1") (pin "2") (pinfunction "K_2") (pintype "passive"))
      (node (ref "S12_D2") (pin "1") (pinfunction "A_1") (pintype "passive"))
    )
    (net (code "26") (name "Net-(S12_C2-Positive)") (class "Default")
      (node (ref "S12_C2") (pin "1") (pinfunction "Positive_1") (pintype "power_in"))
      (node (ref "S12_D2") (pin "2") (pinfunction "K_2") (pintype "passive"))
      (node (ref "S12_D3") (pin "1") (pinfunction "A_1") (pintype "passive"))
    )
    (net (code "27") (name "Net-(S13_C1-Positive)") (class "Default")
      (node (ref "S13_C1") (pin "1") (pinfunction "Positive_1") (pintype "power_in"))
      (node (ref "S13_C2") (pin "2") (pinfunction "Ground_2") (pintype "power_in"))
      (node (ref "S13_D1") (pin "2") (pinfunction "K_2") (pintype "passive"))
      (node (ref "S13_D2") (pin "1") (pinfunction "A_1") (pintype "passive"))
    )
    (net (code "28") (name "Net-(S13_C2-Positive)") (class "Default")
      (node (ref "S13_C2") (pin "1") (pinfunction "Positive_1") (pintype "power_in"))
      (node (ref "S13_D2") (pin "2") (pinfunction "K_2") (pintype "passive"))
      (node (ref "S13_D3") (pin "1") (pinfunction "A_1") (pintype "passive"))
    )
    (net (code "29") (name "Net-(S14_C1-Positive)") (class "Default")
      (node (ref "S14_C1") (pin "1") (pinfunction "Positive_1") (pintype "power_in"))
      (node (ref "S14_C2") (pin "2") (pinfunction "Ground_2") (pintype "power_in"))
      (node (ref "S14_D1") (pin "2") (pinfunction "K_2") (pintype "passive"))
      (node (ref "S14_D2") (pin "1") (pinfunction "A_1") (pintype "passive"))
    )
    (net (code "30") (name "Net-(S14_C2-Positive)") (class "Default")
      (node (ref "S14_C2") (pin "1") (pinfunction "Positive_1") (pintype "power_in"))
      (node (ref "S14_D2") (pin "2") (pinfunction "K_2") (pintype "passive"))
      (node (ref "S14_D3") (pin "1") (pinfunction "A_1") (pintype "passive"))
    )
    (net (code "31") (name "Net-(S15_C1-Positive)") (class "Default")
      (node (ref "S15_C1") (pin "1") (pinfunction "Positive_1") (pintype "power_in"))
      (node (ref "S15_C2") (pin "2") (pinfunction "Ground_2") (pintype "power_in"))
      (node (ref "S15_D1") (pin "2") (pinfunction "K_2") (pintype "passive"))
      (node (ref "S15_D2") (pin "1") (pinfunction "A_1") (pintype "passive"))
    )
    (net (code "32") (name "Net-(S15_C2-Positive)") (class "Default")
      (node (ref "S15_C2") (pin "1") (pinfunction "Positive_1") (pintype "power_in"))
      (node (ref "S15_D2") (pin "2") (pinfunction "K_2") (pintype "passive"))
      (node (ref "S15_D3") (pin "1") (pinfunction "A_1") (pintype "passive"))
    )
    (net (code "33") (name "Net-(S16_C1-Positive)") (class "Default")
      (node (ref "S16_C1") (pin "1") (pinfunction "Positive_1") (pintype "power_in"))
      (node (ref "S16_C2") (pin "2") (pinfunction "Ground_2") (pintype "power_in"))
      (node (ref "S16_D1") (pin "2") (pinfunction "K_2") (pintype "passive"))
      (node (ref "S16_D2") (pin "1") (pinfunction "A_1") (pintype "passive"))
    )
    (net (code "34") (name "Net-(S16_C2-Positive)") (class "Default")
      (node (ref "S16_C2") (pin "1") (pinfunction "Positive_1") (pintype "power_in"))
      (node (ref "S16_D2") (pin "2") (pinfunction "K_2") (pintype "passive"))
      (node (ref "S16_D3") (pin "1") (pinfunction "A_1") (pintype "passive"))
    )
    (net (code "35") (name "Net-(S17_C1-Positive)") (class "Default")
      (node (ref "S17_C1") (pin "1") (pinfunction "Positive_1") (pintype "power_in"))
      (node (ref "S17_C2") (pin "2") (pinfunction "Ground_2") (pintype "power_in"))
      (node (ref "S17_D1") (pin "2") (pinfunction "K_2") (pintype "passive"))
      (node (ref "S17_D2") (pin "1") (pinfunction "A_1") (pintype "passive"))
    )
    (net (code "36") (name "Net-(S17_C2-Positive)") (class "Default")
      (node (ref "S17_C2") (pin "1") (pinfunction "Positive_1") (pintype "power_in"))
      (node (ref "S17_D2") (pin "2") (pinfunction "K_2") (pintype "passive"))
      (node (ref "S17_D3") (pin "1") (pinfunction "A_1") (pintype "passive"))
    )
    (net (code "37") (name "Net-(S18_C1-Positive)") (class "Default")
      (node (ref "S18_C1") (pin "1") (pinfunction "Positive_1") (pintype "power_in"))
      (node (ref "S18_C2") (pin "2") (pinfunction "Ground_2") (pintype "power_in"))
      (node (ref "S18_D1") (pin "2") (pinfunction "K_2") (pintype "passive"))
      (node (ref "S18_D2") (pin "1") (pinfunction "A_1") (pintype "passive"))
    )
    (net (code "38") (name "Net-(S18_C2-Positive)") (class "Default")
      (node (ref "S18_C2") (pin "1") (pinfunction "Positive_1") (pintype "power_in"))
      (node (ref "S18_D2") (pin "2") (pinfunction "K_2") (pintype "passive"))
      (node (ref "S18_D3") (pin "1") (pinfunction "A_1") (pintype "passive"))
    )
    (net (code "39") (name "Net-(S19_C1-Positive)") (class "Default")
      (node (ref "S19_C1") (pin "1") (pinfunction "Positive_1") (pintype "power_in"))
      (node (ref "S19_C2") (pin "2") (pinfunction "Ground_2") (pintype "power_in"))
      (node (ref "S19_D1") (pin "2") (pinfunction "K_2") (pintype "passive"))
      (node (ref "S19_D2") (pin "1") (pinfunction "A_1") (pintype "passive"))
    )
    (net (code "40") (name "Net-(S19_C2-Positive)") (class "Default")
      (node (ref "S19_C2") (pin "1") (pinfunction "Positive_1") (pintype "power_in"))
      (node (ref "S19_D2") (pin "2") (pinfunction "K_2") (pintype "passive"))
      (node (ref "S19_D3") (pin "1") (pinfunction "A_1") (pintype "passive"))
    )
    (net (code "41") (name "Net-(S20_C1-Positive)") (class "Default")
      (node (ref "S20_C1") (pin "1") (pinfunction "Positive_1") (pintype "power_in"))
      (node (ref "S20_C2") (pin "2") (pinfunction "Ground_2") (pintype "power_in"))
      (node (ref "S20_D1") (pin "2") (pinfunction "K_2") (pintype "passive"))
      (node (ref "S20_D2") (pin "1") (pinfunction "A_1") (pintype "passive"))
    )
    (net (code "42") (name "Net-(S20_C2-Positive)") (class "Default")
      (node (ref "S20_C2") (pin "1") (pinfunction "Positive_1") (pintype "power_in"))
      (node (ref "S20_D2") (pin "2") (pinfunction "K_2") (pintype "passive"))
      (node (ref "S20_D3") (pin "1") (pinfunction "A_1") (pintype "passive"))
    )
    (net (code "43") (name "Net-(S21_C1-Positive)") (class "Default")
      (node (ref "S21_C1") (pin "1") (pinfunction "Positive_1") (pintype "power_in"))
      (node (ref "S21_C2") (pin "2") (pinfunction "Ground_2") (pintype "power_in"))
      (node (ref "S21_D1") (pin "2") (pinfunction "K_2") (pintype "passive"))
      (node (ref "S21_D2") (pin "1") (pinfunction "A_1") (pintype "passive"))
    )
    (net (code "44") (name "Net-(S21_C2-Positive)") (class "Default")
      (node (ref "S21_C2") (pin "1") (pinfunction "Positive_1") (pintype "power_in"))
      (node (ref "S21_D2") (pin "2") (pinfunction "K_2") (pintype "passive"))
      (node (ref "S21_D3") (pin "1") (pinfunction "A_1") (pintype "passive"))
    )
  )
)
